# openmv3.net
KiCad netlist of a schematic drawn in EAGLE
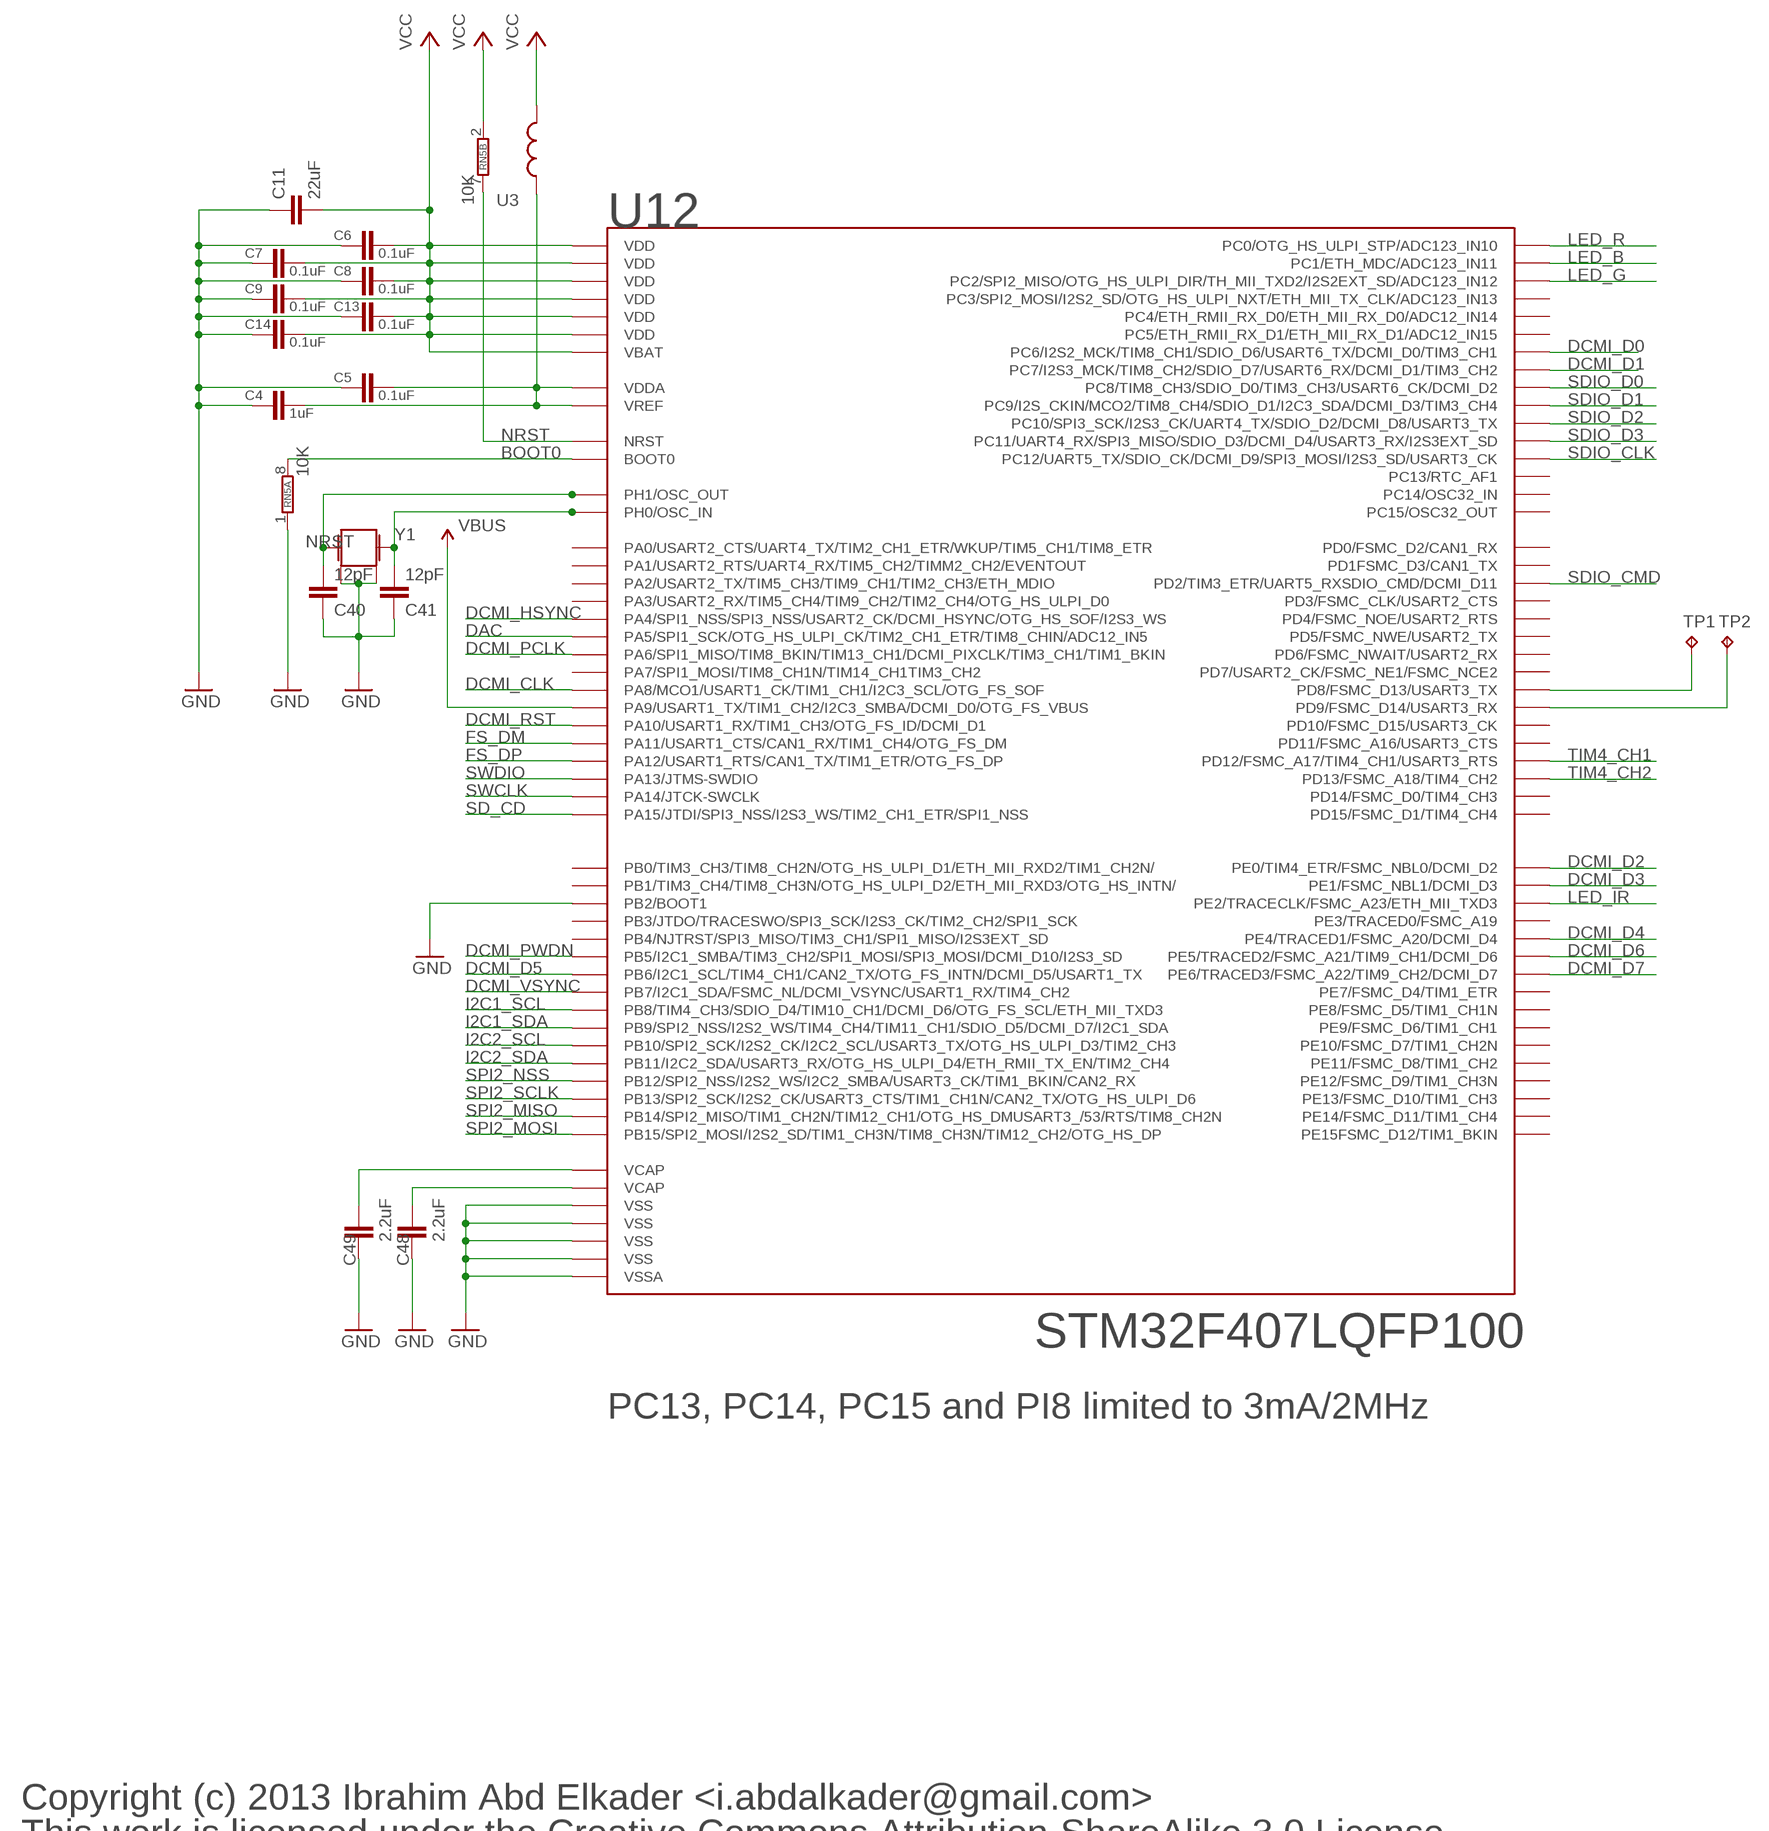
[diagram p0: schematic, sheet 1, part 1 of 2]
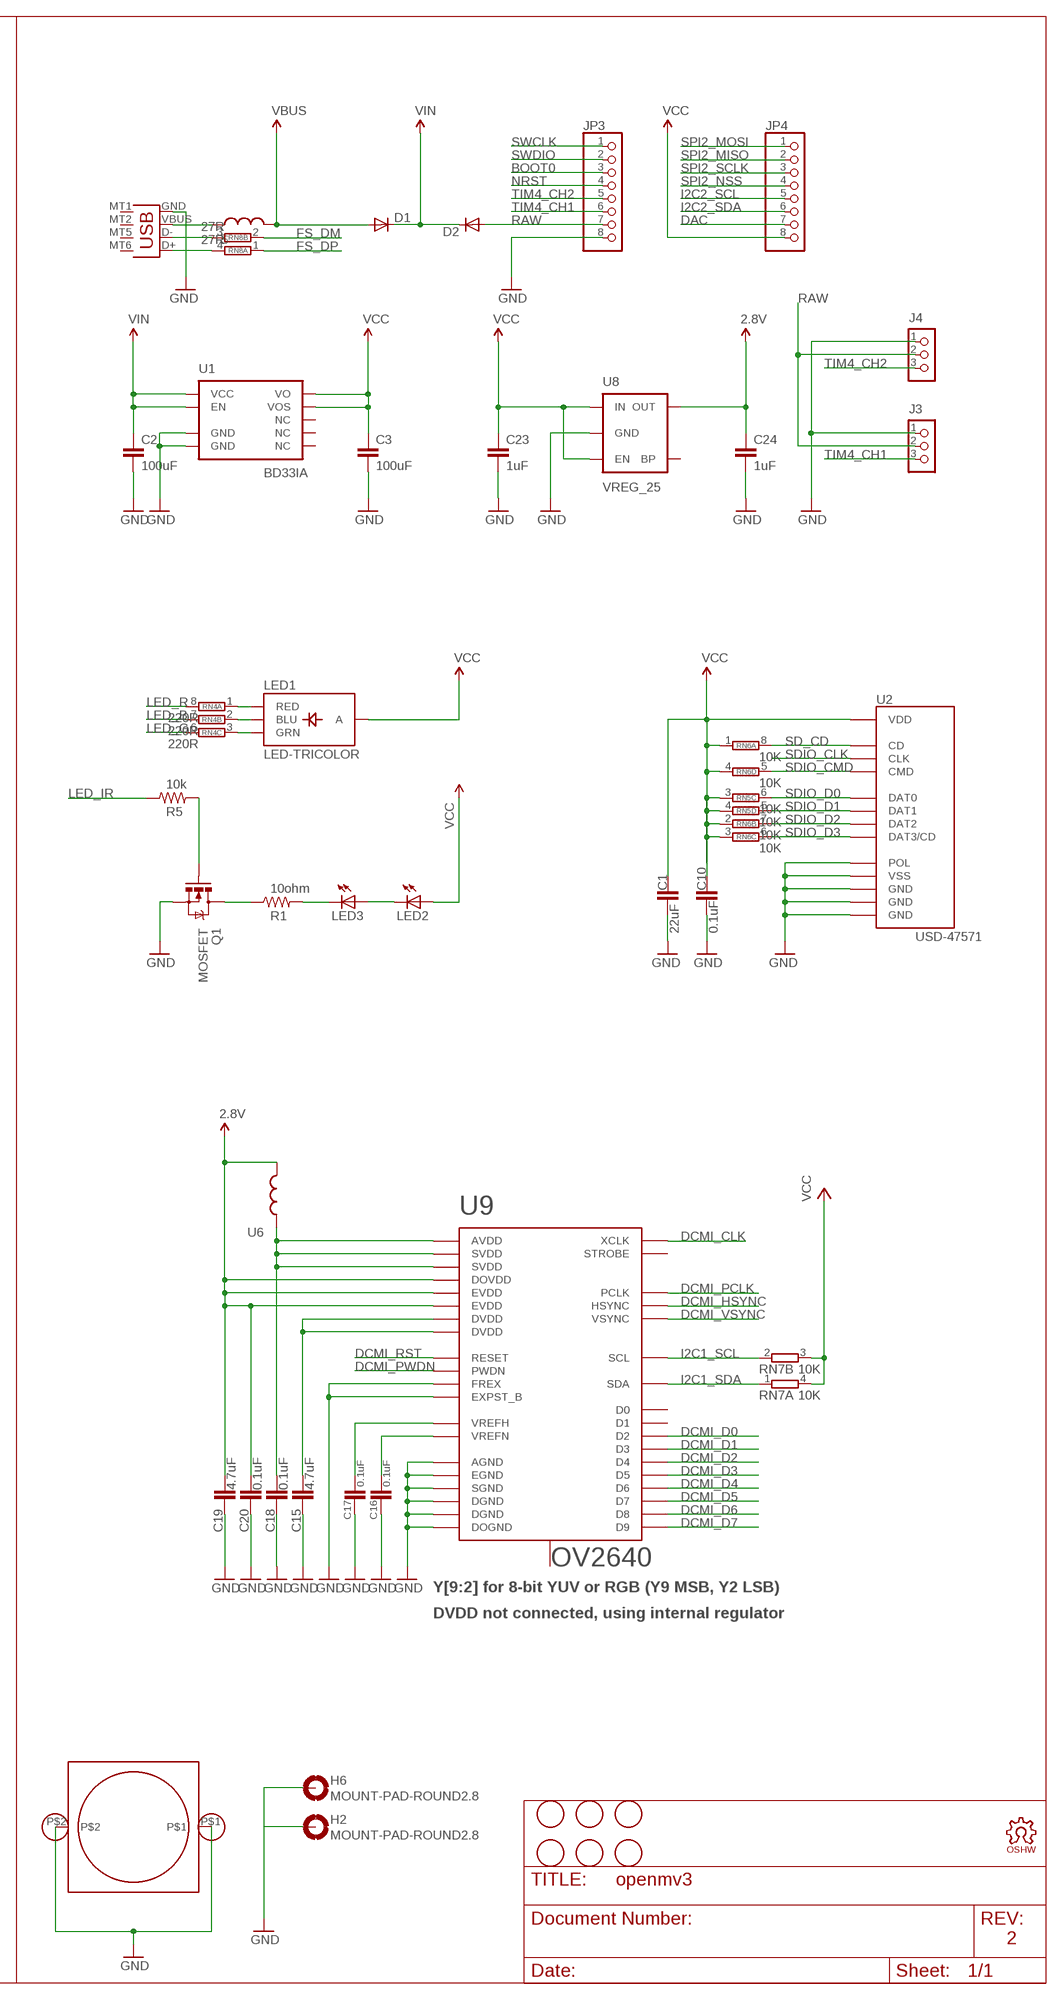
[diagram p1: schematic, sheet 1, part 2 of 2]

(export (version "E")
  (design (tool "Eeschema 10.0.6"))
  (components
    (comp (ref "C1")
      (value "22uF")
      (footprint "eagle-import:0805")
      (libsource (lib "eagle-import") (part "CAP0805"))
    )
    (comp (ref "C2")
      (value "100uF")
      (footprint "eagle-import:1210")
      (libsource (lib "eagle-import") (part "CAP1210"))
    )
    (comp (ref "C3")
      (value "100uF")
      (footprint "eagle-import:1210")
      (libsource (lib "eagle-import") (part "CAP1210"))
    )
    (comp (ref "C4")
      (value "1uF")
      (footprint "eagle-import:0603-CAP")
      (libsource (lib "eagle-import") (part "CAP0603-CAP"))
    )
    (comp (ref "C5")
      (value "0.1uF")
      (footprint "eagle-import:0603-CAP")
      (libsource (lib "eagle-import") (part "CAP0603-CAP"))
    )
    (comp (ref "C6")
      (value "0.1uF")
      (footprint "eagle-import:0603-CAP")
      (libsource (lib "eagle-import") (part "CAP0603-CAP"))
    )
    (comp (ref "C7")
      (value "0.1uF")
      (footprint "eagle-import:0603-CAP")
      (libsource (lib "eagle-import") (part "CAP0603-CAP"))
    )
    (comp (ref "C8")
      (value "0.1uF")
      (footprint "eagle-import:0603-CAP")
      (libsource (lib "eagle-import") (part "CAP0603-CAP"))
    )
    (comp (ref "C9")
      (value "0.1uF")
      (footprint "eagle-import:0603-CAP")
      (libsource (lib "eagle-import") (part "CAP0603-CAP"))
    )
    (comp (ref "C10")
      (value "0.1uF")
      (footprint "eagle-import:0603-CAP")
      (libsource (lib "eagle-import") (part "CAP0603-CAP"))
    )
    (comp (ref "C11")
      (value "22uF")
      (footprint "eagle-import:1206")
      (libsource (lib "eagle-import") (part "CAP1206"))
    )
    (comp (ref "C13")
      (value "0.1uF")
      (footprint "eagle-import:0603-CAP")
      (libsource (lib "eagle-import") (part "CAP0603-CAP"))
    )
    (comp (ref "C14")
      (value "0.1uF")
      (footprint "eagle-import:0603-CAP")
      (libsource (lib "eagle-import") (part "CAP0603-CAP"))
    )
    (comp (ref "C15")
      (value "4.7uF")
      (footprint "eagle-import:0603-CAP")
      (libsource (lib "eagle-import") (part "CAP0603-CAP"))
    )
    (comp (ref "C16")
      (value "0.1uF")
      (footprint "eagle-import:0603-CAP")
      (libsource (lib "eagle-import") (part "CAP0603-CAP"))
    )
    (comp (ref "C17")
      (value "0.1uF")
      (footprint "eagle-import:0603-CAP")
      (libsource (lib "eagle-import") (part "CAP0603-CAP"))
    )
    (comp (ref "C18")
      (value "0.1uF")
      (footprint "eagle-import:0603-CAP")
      (libsource (lib "eagle-import") (part "CAP0603-CAP"))
    )
    (comp (ref "C19")
      (value "4.7uF")
      (footprint "eagle-import:0603-CAP")
      (libsource (lib "eagle-import") (part "CAP0603-CAP"))
    )
    (comp (ref "C20")
      (value "0.1uF")
      (footprint "eagle-import:0603-CAP")
      (libsource (lib "eagle-import") (part "CAP0603-CAP"))
    )
    (comp (ref "C23")
      (value "1uF")
      (footprint "eagle-import:0603-CAP")
      (libsource (lib "eagle-import") (part "CAP0603-CAP"))
    )
    (comp (ref "C24")
      (value "1uF")
      (footprint "eagle-import:0603-CAP")
      (libsource (lib "eagle-import") (part "CAP0603-CAP"))
    )
    (comp (ref "C40")
      (value "12pF")
      (footprint "eagle-import:0603-CAP")
      (libsource (lib "eagle-import") (part "CAP0603-CAP"))
    )
    (comp (ref "C41")
      (value "12pF")
      (footprint "eagle-import:0603-CAP")
      (libsource (lib "eagle-import") (part "CAP0603-CAP"))
    )
    (comp (ref "C48")
      (value "2.2uF")
      (footprint "eagle-import:0603-CAP")
      (libsource (lib "eagle-import") (part "CAP0603-CAP"))
    )
    (comp (ref "C49")
      (value "2.2uF")
      (footprint "eagle-import:0603-CAP")
      (libsource (lib "eagle-import") (part "CAP0603-CAP"))
    )
    (comp (ref "D1")
      (value "DIODESOD")
      (footprint "eagle-import:SOD-323")
      (libsource (lib "eagle-import") (part "DIODESOD"))
    )
    (comp (ref "D2")
      (value "DIODESOD")
      (footprint "eagle-import:SOD-323")
      (libsource (lib "eagle-import") (part "DIODESOD"))
    )
    (comp (ref "H2")
      (value "MOUNT-PAD-ROUND2.8")
      (footprint "eagle-import:2,8-PAD")
      (libsource (lib "eagle-import") (part "MOUNT-PAD-ROUND2.8"))
    )
    (comp (ref "H6")
      (value "MOUNT-PAD-ROUND2.8")
      (footprint "eagle-import:2,8-PAD")
      (libsource (lib "eagle-import") (part "MOUNT-PAD-ROUND2.8"))
    )
    (comp (ref "J3")
      (value "CON_HEADER_1X03")
      (footprint "eagle-import:M1X3_SMD")
      (libsource (lib "eagle-import") (part "CON_HEADER_1X03"))
    )
    (comp (ref "J4")
      (value "CON_HEADER_1X03")
      (footprint "eagle-import:M1X3_SMD")
      (libsource (lib "eagle-import") (part "CON_HEADER_1X03"))
    )
    (comp (ref "JP3")
      (value "PINHD-1X8")
      (footprint "eagle-import:1X08")
      (libsource (lib "eagle-import") (part "PINHD-1X8"))
    )
    (comp (ref "JP4")
      (value "PINHD-1X8")
      (footprint "eagle-import:1X08")
      (libsource (lib "eagle-import") (part "PINHD-1X8"))
    )
    (comp (ref "LED1")
      (value "LED-TRICOLOR")
      (footprint "eagle-import:LED-TRICOLOR-SMD")
      (libsource (lib "eagle-import") (part "LED-TRICOLOR"))
    )
    (comp (ref "LED2")
      (value "LED3MM")
      (footprint "eagle-import:LED3MM")
      (libsource (lib "eagle-import") (part "LED3MM"))
    )
    (comp (ref "LED3")
      (value "LED3MM")
      (footprint "eagle-import:LED3MM")
      (libsource (lib "eagle-import") (part "LED3MM"))
    )
    (comp (ref "LOGO1")
      (value "OSHW_LOGO_FILLX0150-NT")
      (footprint "eagle-import:OSHW_FILLX150_NOTEXT")
      (libsource (lib "eagle-import") (part "OSHW_LOGO_FILLX0150-NT"))
    )
    (comp (ref "Q1")
      (value "MOSFET")
      (footprint "eagle-import:SOT23-3")
      (libsource (lib "eagle-import") (part "MOSFET-NCHANNELSMD"))
    )
    (comp (ref "R1")
      (value "10ohm")
      (footprint "eagle-import:0603-RES")
      (libsource (lib "eagle-import") (part "RESISTOR0603-RES"))
    )
    (comp (ref "R5")
      (value "10k")
      (footprint "eagle-import:0603-RES")
      (libsource (lib "eagle-import") (part "RESISTOR0603-RES"))
    )
    (comp (ref "RN4")
      (value "220R")
      (footprint "eagle-import:EXBV8V")
      (fields (field (name "OC_FARNELL") "unknown") (field (name "OC_NEWARK") "unknown"))
      (libsource (lib "eagle-import") (part "4R-NEXBV8V"))
    )
    (comp (ref "RN5")
      (value "10K")
      (footprint "eagle-import:EXBV8V")
      (fields (field (name "OC_FARNELL") "unknown") (field (name "OC_NEWARK") "unknown"))
      (libsource (lib "eagle-import") (part "4R-NEXBV8V"))
    )
    (comp (ref "RN6")
      (value "10K")
      (footprint "eagle-import:EXBV8V")
      (fields (field (name "OC_FARNELL") "unknown") (field (name "OC_NEWARK") "unknown"))
      (libsource (lib "eagle-import") (part "4R-NEXBV8V"))
    )
    (comp (ref "RN7")
      (value "10K")
      (footprint "eagle-import:EXBV4V")
      (libsource (lib "eagle-import") (part "2R-NEXBV4V"))
    )
    (comp (ref "RN8")
      (value "27R")
      (footprint "eagle-import:EXBV4V")
      (libsource (lib "eagle-import") (part "2R-NEXBV4V"))
    )
    (comp (ref "TP1")
      (value "TPTP12R")
      (footprint "eagle-import:TP12R")
      (libsource (lib "eagle-import") (part "TPTP12R"))
    )
    (comp (ref "TP2")
      (value "TPTP12R")
      (footprint "eagle-import:TP12R")
      (libsource (lib "eagle-import") (part "TPTP12R"))
    )
    (comp (ref "U$1")
      (value "LENSMOUNT20MM")
      (footprint "eagle-import:LENSMOUNT-20MM")
      (libsource (lib "eagle-import") (part "LENSMOUNT20MM"))
    )
    (comp (ref "U$14")
      (value "FIDUCIAL")
      (footprint "eagle-import:FIDUCIAL_1MM")
      (libsource (lib "eagle-import") (part "FIDUCIAL"))
    )
    (comp (ref "U$15")
      (value "FIDUCIAL")
      (footprint "eagle-import:FIDUCIAL_1MM")
      (libsource (lib "eagle-import") (part "FIDUCIAL"))
    )
    (comp (ref "U$16")
      (value "FIDUCIAL")
      (footprint "eagle-import:FIDUCIAL_1MM")
      (libsource (lib "eagle-import") (part "FIDUCIAL"))
    )
    (comp (ref "U$17")
      (value "FIDUCIAL")
      (footprint "eagle-import:FIDUCIAL_1MM")
      (libsource (lib "eagle-import") (part "FIDUCIAL"))
    )
    (comp (ref "U$19")
      (value "FIDUCIAL")
      (footprint "eagle-import:FIDUCIAL_1MM")
      (libsource (lib "eagle-import") (part "FIDUCIAL"))
    )
    (comp (ref "U$20")
      (value "FIDUCIAL")
      (footprint "eagle-import:FIDUCIAL_1MM")
      (libsource (lib "eagle-import") (part "FIDUCIAL"))
    )
    (comp (ref "U1")
      (value "BD33IA")
      (footprint "eagle-import:HTSOP-J8")
      (libsource (lib "eagle-import") (part "BD33IA"))
    )
    (comp (ref "U2")
      (value "USD-47571")
      (footprint "eagle-import:USD-47571")
      (libsource (lib "eagle-import") (part "USD-47571"))
    )
    (comp (ref "U3")
      (value "INDUCTOR0603")
      (footprint "eagle-import:0603")
      (libsource (lib "eagle-import") (part "INDUCTOR0603"))
    )
    (comp (ref "U6")
      (value "INDUCTOR0603")
      (footprint "eagle-import:0603")
      (libsource (lib "eagle-import") (part "INDUCTOR0603"))
    )
    (comp (ref "U7")
      (value "INDUCTOR0603")
      (footprint "eagle-import:0603")
      (libsource (lib "eagle-import") (part "INDUCTOR0603"))
    )
    (comp (ref "U8")
      (value "VREG_25")
      (footprint "eagle-import:SOT23-5")
      (libsource (lib "eagle-import") (part "V_REG_LDOSMD"))
    )
    (comp (ref "U9")
      (value "OV2640")
      (footprint "eagle-import:CSP2")
      (libsource (lib "eagle-import") (part "OV2640"))
    )
    (comp (ref "U12")
      (value "STM32F407LQFP100")
      (footprint "eagle-import:LQFP100")
      (libsource (lib "eagle-import") (part "STM32F407LQFP100"))
    )
    (comp (ref "X2")
      (value "USB-MICROB")
      (footprint "eagle-import:USB-MICROB")
      (libsource (lib "eagle-import") (part "USB-MICROB"))
    )
    (comp (ref "Y1")
      (value "CRYSTAL2.5X2.0")
      (footprint "eagle-import:CRYSTAL-2.5X2.0")
      (libsource (lib "eagle-import") (part "CRYSTAL2.5X2.0"))
    )
  )
  (nets
    (net (code "1") (name "/BOOT0") (class "Default")
      (node (ref "JP3") (pin "3") (pinfunction "3_3") (pintype "passive"))
      (node (ref "RN5") (pin "8") (pinfunction "2_8") (pintype "passive"))
      (node (ref "U12") (pin "94") (pinfunction "BOOT0_94") (pintype "bidirectional"))
    )
    (net (code "2") (name "/DAC") (class "Default")
      (node (ref "JP4") (pin "7") (pinfunction "7_7") (pintype "passive"))
      (node (ref "U12") (pin "30") (pinfunction "PA5/SPI1_SCK/OTG_HS_ULPI_CK/TIM2_CH1_ETR/TIM8_CHIN/ADC12_IN5_30") (pintype "bidirectional"))
    )
    (net (code "3") (name "/DCMI_CLK") (class "Default")
      (node (ref "U12") (pin "67") (pinfunction "PA8/MCO1/USART1_CK/TIM1_CH1/I2C3_SCL/OTG_FS_SOF_67") (pintype "bidirectional"))
      (node (ref "U9") (pin "C4") (pinfunction "XCLK_C4") (pintype "bidirectional"))
    )
    (net (code "4") (name "/DCMI_D0") (class "Default")
      (node (ref "U12") (pin "63") (pinfunction "PC6/I2S2_MCK/TIM8_CH1/SDIO_D6/USART6_TX/DCMI_D0/TIM3_CH1_63") (pintype "bidirectional"))
      (node (ref "U9") (pin "F3") (pinfunction "D2_F3") (pintype "bidirectional"))
    )
    (net (code "5") (name "/DCMI_D1") (class "Default")
      (node (ref "U12") (pin "64") (pinfunction "PC7/I2S3_MCK/TIM8_CH2/SDIO_D7/USART6_RX/DCMI_D1/TIM3_CH2_64") (pintype "bidirectional"))
      (node (ref "U9") (pin "G3") (pinfunction "D3_G3") (pintype "bidirectional"))
    )
    (net (code "6") (name "/DCMI_D2") (class "Default")
      (node (ref "U12") (pin "97") (pinfunction "PE0/TIM4_ETR/FSMC_NBL0/DCMI_D2_97") (pintype "bidirectional"))
      (node (ref "U9") (pin "F4") (pinfunction "D4_F4") (pintype "bidirectional"))
    )
    (net (code "7") (name "/DCMI_D3") (class "Default")
      (node (ref "U12") (pin "98") (pinfunction "PE1/FSMC_NBL1/DCMI_D3_98") (pintype "bidirectional"))
      (node (ref "U9") (pin "G4") (pinfunction "D5_G4") (pintype "bidirectional"))
    )
    (net (code "8") (name "/DCMI_D4") (class "Default")
      (node (ref "U12") (pin "3") (pinfunction "PE4/TRACED1/FSMC_A20/DCMI_D4_3") (pintype "bidirectional"))
      (node (ref "U9") (pin "E5") (pinfunction "D6_E5") (pintype "bidirectional"))
    )
    (net (code "9") (name "/DCMI_D5") (class "Default")
      (node (ref "U12") (pin "92") (pinfunction "PB6/I2C1_SCL/TIM4_CH1/CAN2_TX/OTG_FS_INTN/DCMI_D5/USART1_TX_92") (pintype "bidirectional"))
      (node (ref "U9") (pin "G5") (pinfunction "D7_G5") (pintype "bidirectional"))
    )
    (net (code "10") (name "/DCMI_D6") (class "Default")
      (node (ref "U12") (pin "4") (pinfunction "PE5/TRACED2/FSMC_A21/TIM9_CH1/DCMI_D6_4") (pintype "bidirectional"))
      (node (ref "U9") (pin "F5") (pinfunction "D8_F5") (pintype "bidirectional"))
    )
    (net (code "11") (name "/DCMI_D7") (class "Default")
      (node (ref "U12") (pin "5") (pinfunction "PE6/TRACED3/FSMC_A22/TIM9_CH2/DCMI_D7_5") (pintype "bidirectional"))
      (node (ref "U9") (pin "G6") (pinfunction "D9_G6") (pintype "bidirectional"))
    )
    (net (code "12") (name "/DCMI_HSYNC") (class "Default")
      (node (ref "U12") (pin "29") (pinfunction "PA4/SPI1_NSS/SPI3_NSS/USART2_CK/DCMI_HSYNC/OTG_HS_SOF/I2S3_WS_29") (pintype "bidirectional"))
      (node (ref "U9") (pin "C3") (pinfunction "HSYNC_C3") (pintype "bidirectional"))
    )
    (net (code "13") (name "/DCMI_PCLK") (class "Default")
      (node (ref "U12") (pin "31") (pinfunction "PA6/SPI1_MISO/TIM8_BKIN/TIM13_CH1/DCMI_PIXCLK/TIM3_CH1/TIM1_BKIN_31") (pintype "bidirectional"))
      (node (ref "U9") (pin "E3") (pinfunction "PCLK_E3") (pintype "bidirectional"))
    )
    (net (code "14") (name "/DCMI_PWDN") (class "Default")
      (node (ref "U12") (pin "91") (pinfunction "PB5/I2C1_SMBA/TIM3_CH2/SPI1_MOSI/SPI3_MOSI/DCMI_D10/I2S3_SD_91") (pintype "bidirectional"))
      (node (ref "U9") (pin "B6") (pinfunction "PWDN_B6") (pintype "bidirectional"))
    )
    (net (code "15") (name "/DCMI_RST") (class "Default")
      (node (ref "U12") (pin "69") (pinfunction "PA10/USART1_RX/TIM1_CH3/OTG_FS_ID/DCMI_D1_69") (pintype "bidirectional"))
      (node (ref "U9") (pin "C6") (pinfunction "RESET_C6") (pintype "bidirectional"))
    )
    (net (code "16") (name "/DCMI_VSYNC") (class "Default")
      (node (ref "U12") (pin "93") (pinfunction "PB7/I2C1_SDA/FSMC_NL/DCMI_VSYNC/USART1_RX/TIM4_CH2_93") (pintype "bidirectional"))
      (node (ref "U9") (pin "D2") (pinfunction "VSYNC_D2") (pintype "bidirectional"))
    )
    (net (code "17") (name "/FS_DM") (class "Default")
      (node (ref "RN8") (pin "2") (pinfunction "1_2") (pintype "passive"))
      (node (ref "U12") (pin "70") (pinfunction "PA11/USART1_CTS/CAN1_RX/TIM1_CH4/OTG_FS_DM_70") (pintype "bidirectional"))
    )
    (net (code "18") (name "/FS_DP") (class "Default")
      (node (ref "RN8") (pin "1") (pinfunction "1_1") (pintype "passive"))
      (node (ref "U12") (pin "71") (pinfunction "PA12/USART1_RTS/CAN1_TX/TIM1_ETR/OTG_FS_DP_71") (pintype "bidirectional"))
    )
    (net (code "19") (name "/I2C1_SCL") (class "Default")
      (node (ref "RN7") (pin "2") (pinfunction "1_2") (pintype "passive"))
      (node (ref "U12") (pin "95") (pinfunction "PB8/TIM4_CH3/SDIO_D4/TIM10_CH1/DCMI_D6/OTG_FS_SCL/ETH_MII_TXD3_95") (pintype "bidirectional"))
      (node (ref "U9") (pin "C2") (pinfunction "SCL_C2") (pintype "bidirectional"))
    )
    (net (code "20") (name "/I2C1_SDA") (class "Default")
      (node (ref "RN7") (pin "1") (pinfunction "1_1") (pintype "passive"))
      (node (ref "U12") (pin "96") (pinfunction "PB9/SPI2_NSS/I2S2_WS/TIM4_CH4/TIM11_CH1/SDIO_D5/DCMI_D7/I2C1_SDA_96") (pintype "bidirectional"))
      (node (ref "U9") (pin "C1") (pinfunction "SDA_C1") (pintype "bidirectional"))
    )
    (net (code "21") (name "/I2C2_SCL") (class "Default")
      (node (ref "JP4") (pin "5") (pinfunction "5_5") (pintype "passive"))
      (node (ref "U12") (pin "47") (pinfunction "PB10/SPI2_SCK/I2S2_CK/I2C2_SCL/USART3_TX/OTG_HS_ULPI_D3/TIM2_CH3_47") (pintype "bidirectional"))
    )
    (net (code "22") (name "/I2C2_SDA") (class "Default")
      (node (ref "JP4") (pin "6") (pinfunction "6_6") (pintype "passive"))
      (node (ref "U12") (pin "48") (pinfunction "PB11/I2C2_SDA/USART3_RX/OTG_HS_ULPI_D4/ETH_RMII_TX_EN/TIM2_CH4_48") (pintype "bidirectional"))
    )
    (net (code "23") (name "/LED_B") (class "Default")
      (node (ref "RN4") (pin "7") (pinfunction "2_7") (pintype "passive"))
      (node (ref "U12") (pin "16") (pinfunction "PC1/ETH_MDC/ADC123_IN11_16") (pintype "bidirectional"))
    )
    (net (code "24") (name "/LED_G") (class "Default")
      (node (ref "RN4") (pin "6") (pinfunction "2_6") (pintype "passive"))
      (node (ref "U12") (pin "17") (pinfunction "PC2/SPI2_MISO/OTG_HS_ULPI_DIR/TH_MII_TXD2/I2S2EXT_SD/ADC123_IN12_17") (pintype "bidirectional"))
    )
    (net (code "25") (name "/LED_IR") (class "Default")
      (node (ref "R5") (pin "1") (pinfunction "1_1") (pintype "passive"))
      (node (ref "U12") (pin "1") (pinfunction "PE2/TRACECLK/FSMC_A23/ETH_MII_TXD3_1") (pintype "bidirectional"))
    )
    (net (code "26") (name "/LED_R") (class "Default")
      (node (ref "RN4") (pin "8") (pinfunction "2_8") (pintype "passive"))
      (node (ref "U12") (pin "15") (pinfunction "PC0/OTG_HS_ULPI_STP/ADC123_IN10_15") (pintype "bidirectional"))
    )
    (net (code "27") (name "/NRST") (class "Default")
      (node (ref "JP3") (pin "4") (pinfunction "4_4") (pintype "passive"))
      (node (ref "RN5") (pin "7") (pinfunction "2_7") (pintype "passive"))
      (node (ref "U12") (pin "14") (pinfunction "NRST_14") (pintype "bidirectional"))
    )
    (net (code "28") (name "/RAW") (class "Default")
      (node (ref "D2") (pin "2") (pinfunction "A_2") (pintype "passive"))
      (node (ref "J3") (pin "2") (pinfunction "2_2") (pintype "bidirectional"))
      (node (ref "J4") (pin "2") (pinfunction "2_2") (pintype "bidirectional"))
      (node (ref "JP3") (pin "7") (pinfunction "7_7") (pintype "passive"))
    )
    (net (code "29") (name "/SDIO_CLK") (class "Default")
      (node (ref "U12") (pin "80") (pinfunction "PC12/UART5_TX/SDIO_CK/DCMI_D9/SPI3_MOSI/I2S3_SD/USART3_CK_80") (pintype "bidirectional"))
      (node (ref "U2") (pin "P$5") (pinfunction "CLK_P$5") (pintype "bidirectional"))
    )
    (net (code "30") (name "/SDIO_CMD") (class "Default")
      (node (ref "RN6") (pin "5") (pinfunction "2_5") (pintype "passive"))
      (node (ref "U12") (pin "83") (pinfunction "PD2/TIM3_ETR/UART5_RXSDIO_CMD/DCMI_D11_83") (pintype "bidirectional"))
      (node (ref "U2") (pin "P$3") (pinfunction "CMD_P$3") (pintype "bidirectional"))
    )
    (net (code "31") (name "/SDIO_D0") (class "Default")
      (node (ref "RN5") (pin "6") (pinfunction "2_6") (pintype "passive"))
      (node (ref "U12") (pin "65") (pinfunction "PC8/TIM8_CH3/SDIO_D0/TIM3_CH3/USART6_CK/DCMI_D2_65") (pintype "bidirectional"))
      (node (ref "U2") (pin "P$7") (pinfunction "DAT0_P$7") (pintype "bidirectional"))
    )
    (net (code "32") (name "/SDIO_D1") (class "Default")
      (node (ref "RN5") (pin "5") (pinfunction "2_5") (pintype "passive"))
      (node (ref "U12") (pin "66") (pinfunction "PC9/I2S_CKIN/MCO2/TIM8_CH4/SDIO_D1/I2C3_SDA/DCMI_D3/TIM3_CH4_66") (pintype "bidirectional"))
      (node (ref "U2") (pin "P$8") (pinfunction "DAT1_P$8") (pintype "bidirectional"))
    )
    (net (code "33") (name "/SDIO_D2") (class "Default")
      (node (ref "RN6") (pin "7") (pinfunction "2_7") (pintype "passive"))
      (node (ref "U12") (pin "78") (pinfunction "PC10/SPI3_SCK/I2S3_CK/UART4_TX/SDIO_D2/DCMI_D8/USART3_TX_78") (pintype "bidirectional"))
      (node (ref "U2") (pin "P$1") (pinfunction "DAT2_P$1") (pintype "bidirectional"))
    )
    (net (code "34") (name "/SDIO_D3") (class "Default")
      (node (ref "RN6") (pin "6") (pinfunction "2_6") (pintype "passive"))
      (node (ref "U12") (pin "79") (pinfunction "PC11/UART4_RX/SPI3_MISO/SDIO_D3/DCMI_D4/USART3_RX/I2S3EXT_SD_79") (pintype "bidirectional"))
      (node (ref "U2") (pin "P$2") (pinfunction "DAT3/CD_P$2") (pintype "bidirectional"))
    )
    (net (code "35") (name "/SD_CD") (class "Default")
      (node (ref "RN6") (pin "8") (pinfunction "2_8") (pintype "passive"))
      (node (ref "U12") (pin "77") (pinfunction "PA15/JTDI/SPI3_NSS/I2S3_WS/TIM2_CH1_ETR/SPI1_NSS_77") (pintype "bidirectional"))
      (node (ref "U2") (pin "G$5") (pinfunction "CD_G$5") (pintype "power_in"))
    )
    (net (code "36") (name "/SPI2_MISO") (class "Default")
      (node (ref "JP4") (pin "2") (pinfunction "2_2") (pintype "passive"))
      (node (ref "U12") (pin "53") (pinfunction "PB14/SPI2_MISO/TIM1_CH2N/TIM12_CH1/OTG_HS_DMUSART3_/53/RTS/TIM8_CH2N_53") (pintype "bidirectional"))
    )
    (net (code "37") (name "/SPI2_MOSI") (class "Default")
      (node (ref "JP4") (pin "1") (pinfunction "1_1") (pintype "passive"))
      (node (ref "U12") (pin "54") (pinfunction "PB15/SPI2_MOSI/I2S2_SD/TIM1_CH3N/TIM8_CH3N/TIM12_CH2/OTG_HS_DP_54") (pintype "bidirectional"))
    )
    (net (code "38") (name "/SPI2_NSS") (class "Default")
      (node (ref "JP4") (pin "4") (pinfunction "4_4") (pintype "passive"))
      (node (ref "U12") (pin "51") (pinfunction "PB12/SPI2_NSS/I2S2_WS/I2C2_SMBA/USART3_CK/TIM1_BKIN/CAN2_RX_51") (pintype "bidirectional"))
    )
    (net (code "39") (name "/SPI2_SCLK") (class "Default")
      (node (ref "JP4") (pin "3") (pinfunction "3_3") (pintype "passive"))
      (node (ref "U12") (pin "52") (pinfunction "PB13/SPI2_SCK/I2S2_CK/USART3_CTS/TIM1_CH1N/CAN2_TX/OTG_HS_ULPI_D6_52") (pintype "bidirectional"))
    )
    (net (code "40") (name "/SWCLK") (class "Default")
      (node (ref "JP3") (pin "1") (pinfunction "1_1") (pintype "passive"))
      (node (ref "U12") (pin "76") (pinfunction "PA14/JTCK-SWCLK_76") (pintype "bidirectional"))
    )
    (net (code "41") (name "/SWDIO") (class "Default")
      (node (ref "JP3") (pin "2") (pinfunction "2_2") (pintype "passive"))
      (node (ref "U12") (pin "72") (pinfunction "PA13/JTMS-SWDIO_72") (pintype "bidirectional"))
    )
    (net (code "42") (name "/TIM4_CH1") (class "Default")
      (node (ref "J3") (pin "3") (pinfunction "3_3") (pintype "bidirectional"))
      (node (ref "JP3") (pin "6") (pinfunction "6_6") (pintype "passive"))
      (node (ref "U12") (pin "59") (pinfunction "PD12/FSMC_A17/TIM4_CH1/USART3_RTS_59") (pintype "bidirectional"))
    )
    (net (code "43") (name "/TIM4_CH2") (class "Default")
      (node (ref "J4") (pin "3") (pinfunction "3_3") (pintype "bidirectional"))
      (node (ref "JP3") (pin "5") (pinfunction "5_5") (pintype "passive"))
      (node (ref "U12") (pin "60") (pinfunction "PD13/FSMC_A18/TIM4_CH2_60") (pintype "bidirectional"))
    )
    (net (code "44") (name "2.8V") (class "Default")
      (node (ref "C19") (pin "1") (pinfunction "1_1") (pintype "passive"))
      (node (ref "C20") (pin "1") (pinfunction "1_1") (pintype "passive"))
      (node (ref "C24") (pin "1") (pinfunction "1_1") (pintype "passive"))
      (node (ref "U6") (pin "2") (pinfunction "2_2") (pintype "passive"))
      (node (ref "U8") (pin "5") (pinfunction "OUT_5") (pintype "passive"))
      (node (ref "U9") (pin "B1") (pinfunction "DOVDD_B1") (pintype "power_in"))
      (node (ref "U9") (pin "F1") (pinfunction "EVDD_F1") (pintype "power_in"))
      (node (ref "U9") (pin "G1") (pinfunction "EVDD_G1") (pintype "power_in"))
    )
    (net (code "45") (name "GND") (class "Default")
      (node (ref "C1") (pin "2") (pinfunction "2_2") (pintype "passive"))
      (node (ref "C10") (pin "2") (pinfunction "2_2") (pintype "passive"))
      (node (ref "C11") (pin "1") (pinfunction "1_1") (pintype "passive"))
      (node (ref "C13") (pin "2") (pinfunction "2_2") (pintype "passive"))
      (node (ref "C14") (pin "2") (pinfunction "2_2") (pintype "passive"))
      (node (ref "C15") (pin "2") (pinfunction "2_2") (pintype "passive"))
      (node (ref "C16") (pin "2") (pinfunction "2_2") (pintype "passive"))
      (node (ref "C17") (pin "2") (pinfunction "2_2") (pintype "passive"))
      (node (ref "C18") (pin "2") (pinfunction "2_2") (pintype "passive"))
      (node (ref "C19") (pin "2") (pinfunction "2_2") (pintype "passive"))
      (node (ref "C2") (pin "2") (pinfunction "2_2") (pintype "passive"))
      (node (ref "C20") (pin "2") (pinfunction "2_2") (pintype "passive"))
      (node (ref "C23") (pin "2") (pinfunction "2_2") (pintype "passive"))
      (node (ref "C24") (pin "2") (pinfunction "2_2") (pintype "passive"))
      (node (ref "C3") (pin "2") (pinfunction "2_2") (pintype "passive"))
      (node (ref "C4") (pin "2") (pinfunction "2_2") (pintype "passive"))
      (node (ref "C40") (pin "1") (pinfunction "1_1") (pintype "passive"))
      (node (ref "C41") (pin "1") (pinfunction "1_1") (pintype "passive"))
      (node (ref "C48") (pin "2") (pinfunction "2_2") (pintype "passive"))
      (node (ref "C49") (pin "2") (pinfunction "2_2") (pintype "passive"))
      (node (ref "C5") (pin "2") (pinfunction "2_2") (pintype "passive"))
      (node (ref "C6") (pin "2") (pinfunction "2_2") (pintype "passive"))
      (node (ref "C7") (pin "2") (pinfunction "2_2") (pintype "passive"))
      (node (ref "C8") (pin "2") (pinfunction "2_2") (pintype "passive"))
      (node (ref "C9") (pin "2") (pinfunction "2_2") (pintype "passive"))
      (node (ref "H2") (pin "B2,8") (pinfunction "MOUNT_B2,8") (pintype "passive"))
      (node (ref "H6") (pin "B2,8") (pinfunction "MOUNT_B2,8") (pintype "passive"))
      (node (ref "J3") (pin "1") (pinfunction "1_1") (pintype "bidirectional"))
      (node (ref "J4") (pin "1") (pinfunction "1_1") (pintype "bidirectional"))
      (node (ref "JP3") (pin "8") (pinfunction "8_8") (pintype "passive"))
      (node (ref "Q1") (pin "2") (pinfunction "S_2") (pintype "passive"))
      (node (ref "RN5") (pin "1") (pinfunction "1_1") (pintype "passive"))
      (node (ref "U$1") (pin "P$1") (pinfunction "P$1_P$1") (pintype "power_in"))
      (node (ref "U$1") (pin "P$2") (pinfunction "P$2_P$2") (pintype "power_in"))
      (node (ref "U1") (pin "3") (pinfunction "GND_3") (pintype "input"))
      (node (ref "U1") (pin "P$1") (pinfunction "GND_P$1") (pintype "input"))
      (node (ref "U12") (pin "10") (pinfunction "VSS_10") (pintype "power_in"))
      (node (ref "U12") (pin "20") (pinfunction "VSSA_20") (pintype "power_in"))
      (node (ref "U12") (pin "27") (pinfunction "VSS_27") (pintype "power_in"))
      (node (ref "U12") (pin "37") (pinfunction "PB2/BOOT1_37") (pintype "bidirectional"))
      (node (ref "U12") (pin "74") (pinfunction "VSS_74") (pintype "power_in"))
      (node (ref "U12") (pin "99") (pinfunction "VSS_99") (pintype "power_in"))
      (node (ref "U2") (pin "G$1") (pinfunction "GND_G$1") (pintype "power_in"))
      (node (ref "U2") (pin "G$2") (pinfunction "GND_G$2") (pintype "power_in"))
      (node (ref "U2") (pin "G$3") (pinfunction "GND_G$3") (pintype "power_in"))
      (node (ref "U2") (pin "G$4") (pinfunction "POL_G$4") (pintype "power_in"))
      (node (ref "U2") (pin "P$6") (pinfunction "VSS_P$6") (pintype "power_in"))
      (node (ref "U8") (pin "2") (pinfunction "GND_2") (pintype "input"))
      (node (ref "U9") (pin "A1") (pinfunction "DOGND_A1") (pintype "power_in"))
      (node (ref "U9") (pin "A2") (pinfunction "EXPST_B_A2") (pintype "output"))
      (node (ref "U9") (pin "A3") (pinfunction "AGND_A3") (pintype "power_in"))
      (node (ref "U9") (pin "A4") (pinfunction "SGND_A4") (pintype "power_in"))
      (node (ref "U9") (pin "B2") (pinfunction "FREX_B2") (pintype "input"))
      (node (ref "U9") (pin "E4") (pinfunction "EGND_E4") (pintype "power_in"))
      (node (ref "U9") (pin "E6") (pinfunction "DGND_E6") (pintype "power_in"))
      (node (ref "U9") (pin "G2") (pinfunction "DGND_G2") (pintype "power_in"))
      (node (ref "X2") (pin "GND") (pinfunction "GND_GND") (pintype "bidirectional"))
      (node (ref "Y1") (pin "2") (pinfunction "P$1_2") (pintype "power_in"))
      (node (ref "Y1") (pin "4") (pinfunction "P$2_4") (pintype "power_in"))
    )
    (net (code "46") (name "Net-(C15-Pad1)") (class "Default")
      (node (ref "C15") (pin "1") (pinfunction "1_1") (pintype "passive"))
      (node (ref "U9") (pin "F2") (pinfunction "DVDD_F2") (pintype "power_in"))
      (node (ref "U9") (pin "F6") (pinfunction "DVDD_F6") (pintype "power_in"))
    )
    (net (code "47") (name "Net-(C48-Pad1)") (class "Default")
      (node (ref "C48") (pin "1") (pinfunction "1_1") (pintype "passive"))
      (node (ref "U12") (pin "73") (pinfunction "VCAP_73") (pintype "power_in"))
    )
    (net (code "48") (name "Net-(C49-Pad1)") (class "Default")
      (node (ref "C49") (pin "1") (pinfunction "1_1") (pintype "passive"))
      (node (ref "U12") (pin "49") (pinfunction "VCAP_49") (pintype "power_in"))
    )
    (net (code "49") (name "Net-(LED1-BLU)") (class "Default")
      (node (ref "LED1") (pin "B") (pinfunction "BLU_B") (pintype "bidirectional"))
      (node (ref "RN4") (pin "2") (pinfunction "1_2") (pintype "passive"))
    )
    (net (code "50") (name "Net-(LED1-GRN)") (class "Default")
      (node (ref "LED1") (pin "G") (pinfunction "GRN_G") (pintype "bidirectional"))
      (node (ref "RN4") (pin "3") (pinfunction "1_3") (pintype "passive"))
    )
    (net (code "51") (name "Net-(LED1-RED)") (class "Default")
      (node (ref "LED1") (pin "R") (pinfunction "RED_R") (pintype "bidirectional"))
      (node (ref "RN4") (pin "1") (pinfunction "1_1") (pintype "passive"))
    )
    (net (code "52") (name "Net-(LED2-C)") (class "Default")
      (node (ref "LED2") (pin "K") (pinfunction "C_K") (pintype "passive"))
      (node (ref "LED3") (pin "A") (pinfunction "A_A") (pintype "passive"))
    )
    (net (code "53") (name "Net-(LED3-C)") (class "Default")
      (node (ref "LED3") (pin "K") (pinfunction "C_K") (pintype "passive"))
      (node (ref "R1") (pin "2") (pinfunction "2_2") (pintype "passive"))
    )
    (net (code "54") (name "Net-(Q1-D)") (class "Default")
      (node (ref "Q1") (pin "3") (pinfunction "D_3") (pintype "passive"))
      (node (ref "R1") (pin "1") (pinfunction "1_1") (pintype "passive"))
    )
    (net (code "55") (name "Net-(Q1-G)") (class "Default")
      (node (ref "Q1") (pin "1") (pinfunction "G_1") (pintype "passive"))
      (node (ref "R5") (pin "2") (pinfunction "2_2") (pintype "passive"))
    )
    (net (code "56") (name "Net-(RN8A-2)") (class "Default")
      (node (ref "RN8") (pin "4") (pinfunction "2_4") (pintype "passive"))
      (node (ref "X2") (pin "D+") (pinfunction "D+_D+") (pintype "bidirectional"))
    )
    (net (code "57") (name "Net-(RN8B-2)") (class "Default")
      (node (ref "RN8") (pin "3") (pinfunction "2_3") (pintype "passive"))
      (node (ref "X2") (pin "D-") (pinfunction "D-_D-") (pintype "bidirectional"))
    )
    (net (code "58") (name "Net-(U7-Pad1)") (class "Default")
      (node (ref "U7") (pin "1") (pinfunction "1_1") (pintype "passive"))
      (node (ref "X2") (pin "VBUS") (pinfunction "VBUS_VBUS") (pintype "bidirectional"))
    )
    (net (code "59") (name "Net-(U9-AVDD)") (class "Default")
      (node (ref "C18") (pin "1") (pinfunction "1_1") (pintype "passive"))
      (node (ref "U6") (pin "1") (pinfunction "1_1") (pintype "passive"))
      (node (ref "U9") (pin "B3") (pinfunction "AVDD_B3") (pintype "power_in"))
      (node (ref "U9") (pin "B4") (pinfunction "SVDD_B4") (pintype "power_in"))
      (node (ref "U9") (pin "B5") (pinfunction "SVDD_B5") (pintype "power_in"))
    )
    (net (code "60") (name "Net-(U9-VREFH)") (class "Default")
      (node (ref "C17") (pin "1") (pinfunction "1_1") (pintype "passive"))
      (node (ref "U9") (pin "C5") (pinfunction "VREFH_C5") (pintype "power_in"))
    )
    (net (code "61") (name "Net-(U9-VREFN)") (class "Default")
      (node (ref "C16") (pin "1") (pinfunction "1_1") (pintype "passive"))
      (node (ref "U9") (pin "A5") (pinfunction "VREFN_A5") (pintype "power_in"))
    )
    (net (code "62") (name "Net-(U12-PD8{slash}FSMC_D13{slash}USART3_TX)") (class "Default")
      (node (ref "TP1") (pin "TP") (pinfunction "TP_TP") (pintype "input"))
      (node (ref "U12") (pin "55") (pinfunction "PD8/FSMC_D13/USART3_TX_55") (pintype "bidirectional"))
    )
    (net (code "63") (name "Net-(U12-PD9{slash}FSMC_D14{slash}USART3_RX)") (class "Default")
      (node (ref "TP2") (pin "TP") (pinfunction "TP_TP") (pintype "input"))
      (node (ref "U12") (pin "56") (pinfunction "PD9/FSMC_D14/USART3_RX_56") (pintype "bidirectional"))
    )
    (net (code "64") (name "Net-(U12-PH0{slash}OSC_IN)") (class "Default")
      (node (ref "C41") (pin "2") (pinfunction "2_2") (pintype "passive"))
      (node (ref "U12") (pin "12") (pinfunction "PH0/OSC_IN_12") (pintype "bidirectional"))
      (node (ref "Y1") (pin "1") (pinfunction "1_1") (pintype "passive"))
    )
    (net (code "65") (name "Net-(U12-PH1{slash}OSC_OUT)") (class "Default")
      (node (ref "C40") (pin "2") (pinfunction "2_2") (pintype "passive"))
      (node (ref "U12") (pin "13") (pinfunction "PH1/OSC_OUT_13") (pintype "bidirectional"))
      (node (ref "Y1") (pin "3") (pinfunction "2_3") (pintype "passive"))
    )
    (net (code "66") (name "Net-(U12-VDDA)") (class "Default")
      (node (ref "C4") (pin "1") (pinfunction "1_1") (pintype "passive"))
      (node (ref "C5") (pin "1") (pinfunction "1_1") (pintype "passive"))
      (node (ref "U12") (pin "21") (pinfunction "VREF_21") (pintype "power_in"))
      (node (ref "U12") (pin "22") (pinfunction "VDDA_22") (pintype "power_in"))
      (node (ref "U3") (pin "1") (pinfunction "1_1") (pintype "passive"))
    )
    (net (code "67") (name "VBUS") (class "Default")
      (node (ref "D1") (pin "2") (pinfunction "A_2") (pintype "passive"))
      (node (ref "U12") (pin "68") (pinfunction "PA9/USART1_TX/TIM1_CH2/I2C3_SMBA/DCMI_D0/OTG_FS_VBUS_68") (pintype "bidirectional"))
      (node (ref "U7") (pin "2") (pinfunction "2_2") (pintype "passive"))
    )
    (net (code "68") (name "VCC") (class "Default")
      (node (ref "C1") (pin "1") (pinfunction "1_1") (pintype "passive"))
      (node (ref "C10") (pin "1") (pinfunction "1_1") (pintype "passive"))
      (node (ref "C11") (pin "2") (pinfunction "2_2") (pintype "passive"))
      (node (ref "C13") (pin "1") (pinfunction "1_1") (pintype "passive"))
      (node (ref "C14") (pin "1") (pinfunction "1_1") (pintype "passive"))
      (node (ref "C23") (pin "1") (pinfunction "1_1") (pintype "passive"))
      (node (ref "C3") (pin "1") (pinfunction "1_1") (pintype "passive"))
      (node (ref "C6") (pin "1") (pinfunction "1_1") (pintype "passive"))
      (node (ref "C7") (pin "1") (pinfunction "1_1") (pintype "passive"))
      (node (ref "C8") (pin "1") (pinfunction "1_1") (pintype "passive"))
      (node (ref "C9") (pin "1") (pinfunction "1_1") (pintype "passive"))
      (node (ref "JP4") (pin "8") (pinfunction "8_8") (pintype "passive"))
      (node (ref "LED1") (pin "A") (pinfunction "A_A") (pintype "bidirectional"))
      (node (ref "LED2") (pin "A") (pinfunction "A_A") (pintype "passive"))
      (node (ref "RN5") (pin "2") (pinfunction "1_2") (pintype "passive"))
      (node (ref "RN5") (pin "3") (pinfunction "1_3") (pintype "passive"))
      (node (ref "RN5") (pin "4") (pinfunction "1_4") (pintype "passive"))
      (node (ref "RN6") (pin "1") (pinfunction "1_1") (pintype "passive"))
      (node (ref "RN6") (pin "2") (pinfunction "1_2") (pintype "passive"))
      (node (ref "RN6") (pin "3") (pinfunction "1_3") (pintype "passive"))
      (node (ref "RN6") (pin "4") (pinfunction "1_4") (pintype "passive"))
      (node (ref "RN7") (pin "3") (pinfunction "2_3") (pintype "passive"))
      (node (ref "RN7") (pin "4") (pinfunction "2_4") (pintype "passive"))
      (node (ref "U1") (pin "1") (pinfunction "VO_1") (pintype "output"))
      (node (ref "U1") (pin "2") (pinfunction "VOS_2") (pintype "output"))
      (node (ref "U12") (pin "100") (pinfunction "VDD_100") (pintype "power_in"))
      (node (ref "U12") (pin "11") (pinfunction "VDD_11") (pintype "power_in"))
      (node (ref "U12") (pin "19") (pinfunction "VDD_19") (pintype "power_in"))
      (node (ref "U12") (pin "28") (pinfunction "VDD_28") (pintype "power_in"))
      (node (ref "U12") (pin "50") (pinfunction "VDD_50") (pintype "power_in"))
      (node (ref "U12") (pin "6") (pinfunction "VBAT_6") (pintype "power_in"))
      (node (ref "U12") (pin "75") (pinfunction "VDD_75") (pintype "power_in"))
      (node (ref "U2") (pin "P$4") (pinfunction "VDD_P$4") (pintype "power_in"))
      (node (ref "U3") (pin "2") (pinfunction "2_2") (pintype "passive"))
      (node (ref "U8") (pin "1") (pinfunction "IN_1") (pintype "input"))
      (node (ref "U8") (pin "3") (pinfunction "EN_3") (pintype "input"))
    )
    (net (code "69") (name "VIN") (class "Default")
      (node (ref "C2") (pin "1") (pinfunction "1_1") (pintype "passive"))
      (node (ref "D1") (pin "1") (pinfunction "C_1") (pintype "passive"))
      (node (ref "D2") (pin "1") (pinfunction "C_1") (pintype "passive"))
      (node (ref "U1") (pin "5") (pinfunction "EN_5") (pintype "input"))
      (node (ref "U1") (pin "8") (pinfunction "VCC_8") (pintype "input"))
    )
    (net (code "70") (name "unconnected-(U1-NC-Pad4)") (class "Default")
      (node (ref "U1") (pin "4") (pinfunction "NC_4") (pintype "input"))
    )
    (net (code "71") (name "unconnected-(U1-NC-Pad6)") (class "Default")
      (node (ref "U1") (pin "6") (pinfunction "NC_6") (pintype "bidirectional"))
    )
    (net (code "72") (name "unconnected-(U1-NC-Pad7)") (class "Default")
      (node (ref "U1") (pin "7") (pinfunction "NC_7") (pintype "input"))
    )
    (net (code "73") (name "unconnected-(U8-BP-Pad4)") (class "Default")
      (node (ref "U8") (pin "4") (pinfunction "BP_4") (pintype "input"))
    )
    (net (code "74") (name "unconnected-(U9-D0-PadE2)") (class "Default")
      (node (ref "U9") (pin "E2") (pinfunction "D0_E2") (pintype "bidirectional"))
    )
    (net (code "75") (name "unconnected-(U9-D1-PadE1)") (class "Default")
      (node (ref "U9") (pin "E1") (pinfunction "D1_E1") (pintype "bidirectional"))
    )
    (net (code "76") (name "unconnected-(U9-NC-PadD6)") (class "Default")
      (node (ref "U9") (pin "D6") (pinfunction "NC_D6") (pintype "no_connect"))
    )
    (net (code "77") (name "unconnected-(U9-STROBE-PadA6)") (class "Default")
      (node (ref "U9") (pin "A6") (pinfunction "STROBE_A6") (pintype "output"))
    )
    (net (code "78") (name "unconnected-(U12-PA0{slash}USART2_CTS{slash}UART4_TX{slash}TIM2_CH1_ETR{slash}WKUP{slash}TIM5_CH1{slash}TIM8_ETR-Pad23)") (class "Default")
      (node (ref "U12") (pin "23") (pinfunction "PA0/USART2_CTS/UART4_TX/TIM2_CH1_ETR/WKUP/TIM5_CH1/TIM8_ETR_23") (pintype "bidirectional"))
    )
    (net (code "79") (name "unconnected-(U12-PA1{slash}USART2_RTS{slash}UART4_RX{slash}TIM5_CH2{slash}TIMM2_CH2{slash}EVENTOUT-Pad24)") (class "Default")
      (node (ref "U12") (pin "24") (pinfunction "PA1/USART2_RTS/UART4_RX/TIM5_CH2/TIMM2_CH2/EVENTOUT_24") (pintype "bidirectional"))
    )
    (net (code "80") (name "unconnected-(U12-PA2{slash}USART2_TX{slash}TIM5_CH3{slash}TIM9_CH1{slash}TIM2_CH3{slash}ETH_MDIO-Pad25)") (class "Default")
      (node (ref "U12") (pin "25") (pinfunction "PA2/USART2_TX/TIM5_CH3/TIM9_CH1/TIM2_CH3/ETH_MDIO_25") (pintype "bidirectional"))
    )
    (net (code "81") (name "unconnected-(U12-PA3{slash}USART2_RX{slash}TIM5_CH4{slash}TIM9_CH2{slash}TIM2_CH4{slash}OTG_HS_ULPI_D0-Pad26)") (class "Default")
      (node (ref "U12") (pin "26") (pinfunction "PA3/USART2_RX/TIM5_CH4/TIM9_CH2/TIM2_CH4/OTG_HS_ULPI_D0_26") (pintype "bidirectional"))
    )
    (net (code "82") (name "unconnected-(U12-PA7{slash}SPI1_MOSI{slash}TIM8_CH1N{slash}TIM14_CH1TIM3_CH2-Pad32)") (class "Default")
      (node (ref "U12") (pin "32") (pinfunction "PA7/SPI1_MOSI/TIM8_CH1N/TIM14_CH1TIM3_CH2_32") (pintype "bidirectional"))
    )
    (net (code "83") (name "unconnected-(U12-PB0{slash}TIM3_CH3{slash}TIM8_CH2N{slash}OTG_HS_ULPI_D1{slash}ETH_MII_RXD2{slash}TIM1_CH2N{slash}-Pad35)") (class "Default")
      (node (ref "U12") (pin "35") (pinfunction "PB0/TIM3_CH3/TIM8_CH2N/OTG_HS_ULPI_D1/ETH_MII_RXD2/TIM1_CH2N/_35") (pintype "bidirectional"))
    )
    (net (code "84") (name "unconnected-(U12-PB1{slash}TIM3_CH4{slash}TIM8_CH3N{slash}OTG_HS_ULPI_D2{slash}ETH_MII_RXD3{slash}OTG_HS_INTN{slash}-Pad36)") (class "Default")
      (node (ref "U12") (pin "36") (pinfunction "PB1/TIM3_CH4/TIM8_CH3N/OTG_HS_ULPI_D2/ETH_MII_RXD3/OTG_HS_INTN/_36") (pintype "bidirectional"))
    )
    (net (code "85") (name "unconnected-(U12-PB3{slash}JTDO{slash}TRACESWO{slash}SPI3_SCK{slash}I2S3_CK{slash}TIM2_CH2{slash}SPI1_SCK-Pad89)") (class "Default")
      (node (ref "U12") (pin "89") (pinfunction "PB3/JTDO/TRACESWO/SPI3_SCK/I2S3_CK/TIM2_CH2/SPI1_SCK_89") (pintype "bidirectional"))
    )
    (net (code "86") (name "unconnected-(U12-PB4{slash}NJTRST{slash}SPI3_MISO{slash}TIM3_CH1{slash}SPI1_MISO{slash}I2S3EXT_SD-Pad90)") (class "Default")
      (node (ref "U12") (pin "90") (pinfunction "PB4/NJTRST/SPI3_MISO/TIM3_CH1/SPI1_MISO/I2S3EXT_SD_90") (pintype "bidirectional"))
    )
    (net (code "87") (name "unconnected-(U12-PC3{slash}SPI2_MOSI{slash}I2S2_SD{slash}OTG_HS_ULPI_NXT{slash}ETH_MII_TX_CLK{slash}ADC123_IN13-Pad18)") (class "Default")
      (node (ref "U12") (pin "18") (pinfunction "PC3/SPI2_MOSI/I2S2_SD/OTG_HS_ULPI_NXT/ETH_MII_TX_CLK/ADC123_IN13_18") (pintype "bidirectional"))
    )
    (net (code "88") (name "unconnected-(U12-PC4{slash}ETH_RMII_RX_D0{slash}ETH_MII_RX_D0{slash}ADC12_IN14-Pad33)") (class "Default")
      (node (ref "U12") (pin "33") (pinfunction "PC4/ETH_RMII_RX_D0/ETH_MII_RX_D0/ADC12_IN14_33") (pintype "bidirectional"))
    )
    (net (code "89") (name "unconnected-(U12-PC5{slash}ETH_RMII_RX_D1{slash}ETH_MII_RX_D1{slash}ADC12_IN15-Pad34)") (class "Default")
      (node (ref "U12") (pin "34") (pinfunction "PC5/ETH_RMII_RX_D1/ETH_MII_RX_D1/ADC12_IN15_34") (pintype "bidirectional"))
    )
    (net (code "90") (name "unconnected-(U12-PC13{slash}RTC_AF1-Pad7)") (class "Default")
      (node (ref "U12") (pin "7") (pinfunction "PC13/RTC_AF1_7") (pintype "bidirectional"))
    )
    (net (code "91") (name "unconnected-(U12-PC14{slash}OSC32_IN-Pad8)") (class "Default")
      (node (ref "U12") (pin "8") (pinfunction "PC14/OSC32_IN_8") (pintype "bidirectional"))
    )
    (net (code "92") (name "unconnected-(U12-PC15{slash}OSC32_OUT-Pad9)") (class "Default")
      (node (ref "U12") (pin "9") (pinfunction "PC15/OSC32_OUT_9") (pintype "bidirectional"))
    )
    (net (code "93") (name "unconnected-(U12-PD0{slash}FSMC_D2{slash}CAN1_RX-Pad81)") (class "Default")
      (node (ref "U12") (pin "81") (pinfunction "PD0/FSMC_D2/CAN1_RX_81") (pintype "bidirectional"))
    )
    (net (code "94") (name "unconnected-(U12-PD1FSMC_D3{slash}CAN1_TX-Pad82)") (class "Default")
      (node (ref "U12") (pin "82") (pinfunction "PD1FSMC_D3/CAN1_TX_82") (pintype "bidirectional"))
    )
    (net (code "95") (name "unconnected-(U12-PD3{slash}FSMC_CLK{slash}USART2_CTS-Pad84)") (class "Default")
      (node (ref "U12") (pin "84") (pinfunction "PD3/FSMC_CLK/USART2_CTS_84") (pintype "bidirectional"))
    )
    (net (code "96") (name "unconnected-(U12-PD4{slash}FSMC_NOE{slash}USART2_RTS-Pad85)") (class "Default")
      (node (ref "U12") (pin "85") (pinfunction "PD4/FSMC_NOE/USART2_RTS_85") (pintype "bidirectional"))
    )
    (net (code "97") (name "unconnected-(U12-PD5{slash}FSMC_NWE{slash}USART2_TX-Pad86)") (class "Default")
      (node (ref "U12") (pin "86") (pinfunction "PD5/FSMC_NWE/USART2_TX_86") (pintype "bidirectional"))
    )
    (net (code "98") (name "unconnected-(U12-PD6{slash}FSMC_NWAIT{slash}USART2_RX-Pad87)") (class "Default")
      (node (ref "U12") (pin "87") (pinfunction "PD6/FSMC_NWAIT/USART2_RX_87") (pintype "bidirectional"))
    )
    (net (code "99") (name "unconnected-(U12-PD7{slash}USART2_CK{slash}FSMC_NE1{slash}FSMC_NCE2-Pad88)") (class "Default")
      (node (ref "U12") (pin "88") (pinfunction "PD7/USART2_CK/FSMC_NE1/FSMC_NCE2_88") (pintype "bidirectional"))
    )
    (net (code "100") (name "unconnected-(U12-PD10{slash}FSMC_D15{slash}USART3_CK-Pad57)") (class "Default")
      (node (ref "U12") (pin "57") (pinfunction "PD10/FSMC_D15/USART3_CK_57") (pintype "bidirectional"))
    )
    (net (code "101") (name "unconnected-(U12-PD11{slash}FSMC_A16{slash}USART3_CTS-Pad58)") (class "Default")
      (node (ref "U12") (pin "58") (pinfunction "PD11/FSMC_A16/USART3_CTS_58") (pintype "bidirectional"))
    )
    (net (code "102") (name "unconnected-(U12-PD14{slash}FSMC_D0{slash}TIM4_CH3-Pad61)") (class "Default")
      (node (ref "U12") (pin "61") (pinfunction "PD14/FSMC_D0/TIM4_CH3_61") (pintype "bidirectional"))
    )
    (net (code "103") (name "unconnected-(U12-PD15{slash}FSMC_D1{slash}TIM4_CH4-Pad62)") (class "Default")
      (node (ref "U12") (pin "62") (pinfunction "PD15/FSMC_D1/TIM4_CH4_62") (pintype "bidirectional"))
    )
    (net (code "104") (name "unconnected-(U12-PE3{slash}TRACED0{slash}FSMC_A19-Pad2)") (class "Default")
      (node (ref "U12") (pin "2") (pinfunction "PE3/TRACED0/FSMC_A19_2") (pintype "bidirectional"))
    )
    (net (code "105") (name "unconnected-(U12-PE7{slash}FSMC_D4{slash}TIM1_ETR-Pad38)") (class "Default")
      (node (ref "U12") (pin "38") (pinfunction "PE7/FSMC_D4/TIM1_ETR_38") (pintype "bidirectional"))
    )
    (net (code "106") (name "unconnected-(U12-PE8{slash}FSMC_D5{slash}TIM1_CH1N-Pad39)") (class "Default")
      (node (ref "U12") (pin "39") (pinfunction "PE8/FSMC_D5/TIM1_CH1N_39") (pintype "bidirectional"))
    )
    (net (code "107") (name "unconnected-(U12-PE9{slash}FSMC_D6{slash}TIM1_CH1-Pad40)") (class "Default")
      (node (ref "U12") (pin "40") (pinfunction "PE9/FSMC_D6/TIM1_CH1_40") (pintype "bidirectional"))
    )
    (net (code "108") (name "unconnected-(U12-PE10{slash}FSMC_D7{slash}TIM1_CH2N-Pad41)") (class "Default")
      (node (ref "U12") (pin "41") (pinfunction "PE10/FSMC_D7/TIM1_CH2N_41") (pintype "bidirectional"))
    )
    (net (code "109") (name "unconnected-(U12-PE11{slash}FSMC_D8{slash}TIM1_CH2-Pad42)") (class "Default")
      (node (ref "U12") (pin "42") (pinfunction "PE11/FSMC_D8/TIM1_CH2_42") (pintype "bidirectional"))
    )
    (net (code "110") (name "unconnected-(U12-PE12{slash}FSMC_D9{slash}TIM1_CH3N-Pad43)") (class "Default")
      (node (ref "U12") (pin "43") (pinfunction "PE12/FSMC_D9/TIM1_CH3N_43") (pintype "bidirectional"))
    )
    (net (code "111") (name "unconnected-(U12-PE13{slash}FSMC_D10{slash}TIM1_CH3-Pad44)") (class "Default")
      (node (ref "U12") (pin "44") (pinfunction "PE13/FSMC_D10/TIM1_CH3_44") (pintype "bidirectional"))
    )
    (net (code "112") (name "unconnected-(U12-PE14{slash}FSMC_D11{slash}TIM1_CH4-Pad45)") (class "Default")
      (node (ref "U12") (pin "45") (pinfunction "PE14/FSMC_D11/TIM1_CH4_45") (pintype "bidirectional"))
    )
    (net (code "113") (name "unconnected-(U12-PE15FSMC_D12{slash}TIM1_BKIN-Pad46)") (class "Default")
      (node (ref "U12") (pin "46") (pinfunction "PE15FSMC_D12/TIM1_BKIN_46") (pintype "bidirectional"))
    )
    (net (code "114") (name "unconnected-(X2-GND1-PadMT1)") (class "Default")
      (node (ref "X2") (pin "MT1") (pinfunction "GND1_MT1") (pintype "passive"))
    )
    (net (code "115") (name "unconnected-(X2-GND2-PadMT2)") (class "Default")
      (node (ref "X2") (pin "MT2") (pinfunction "GND2_MT2") (pintype "passive"))
    )
    (net (code "116") (name "unconnected-(X2-GND3-PadMT5)") (class "Default")
      (node (ref "X2") (pin "MT5") (pinfunction "GND3_MT5") (pintype "passive"))
    )
    (net (code "117") (name "unconnected-(X2-GND4-PadMT6)") (class "Default")
      (node (ref "X2") (pin "MT6") (pinfunction "GND4_MT6") (pintype "passive"))
    )
  )
)
